# NSE2022_IMGPS_ver0.net
KiCad netlist of a schematic drawn in EAGLE
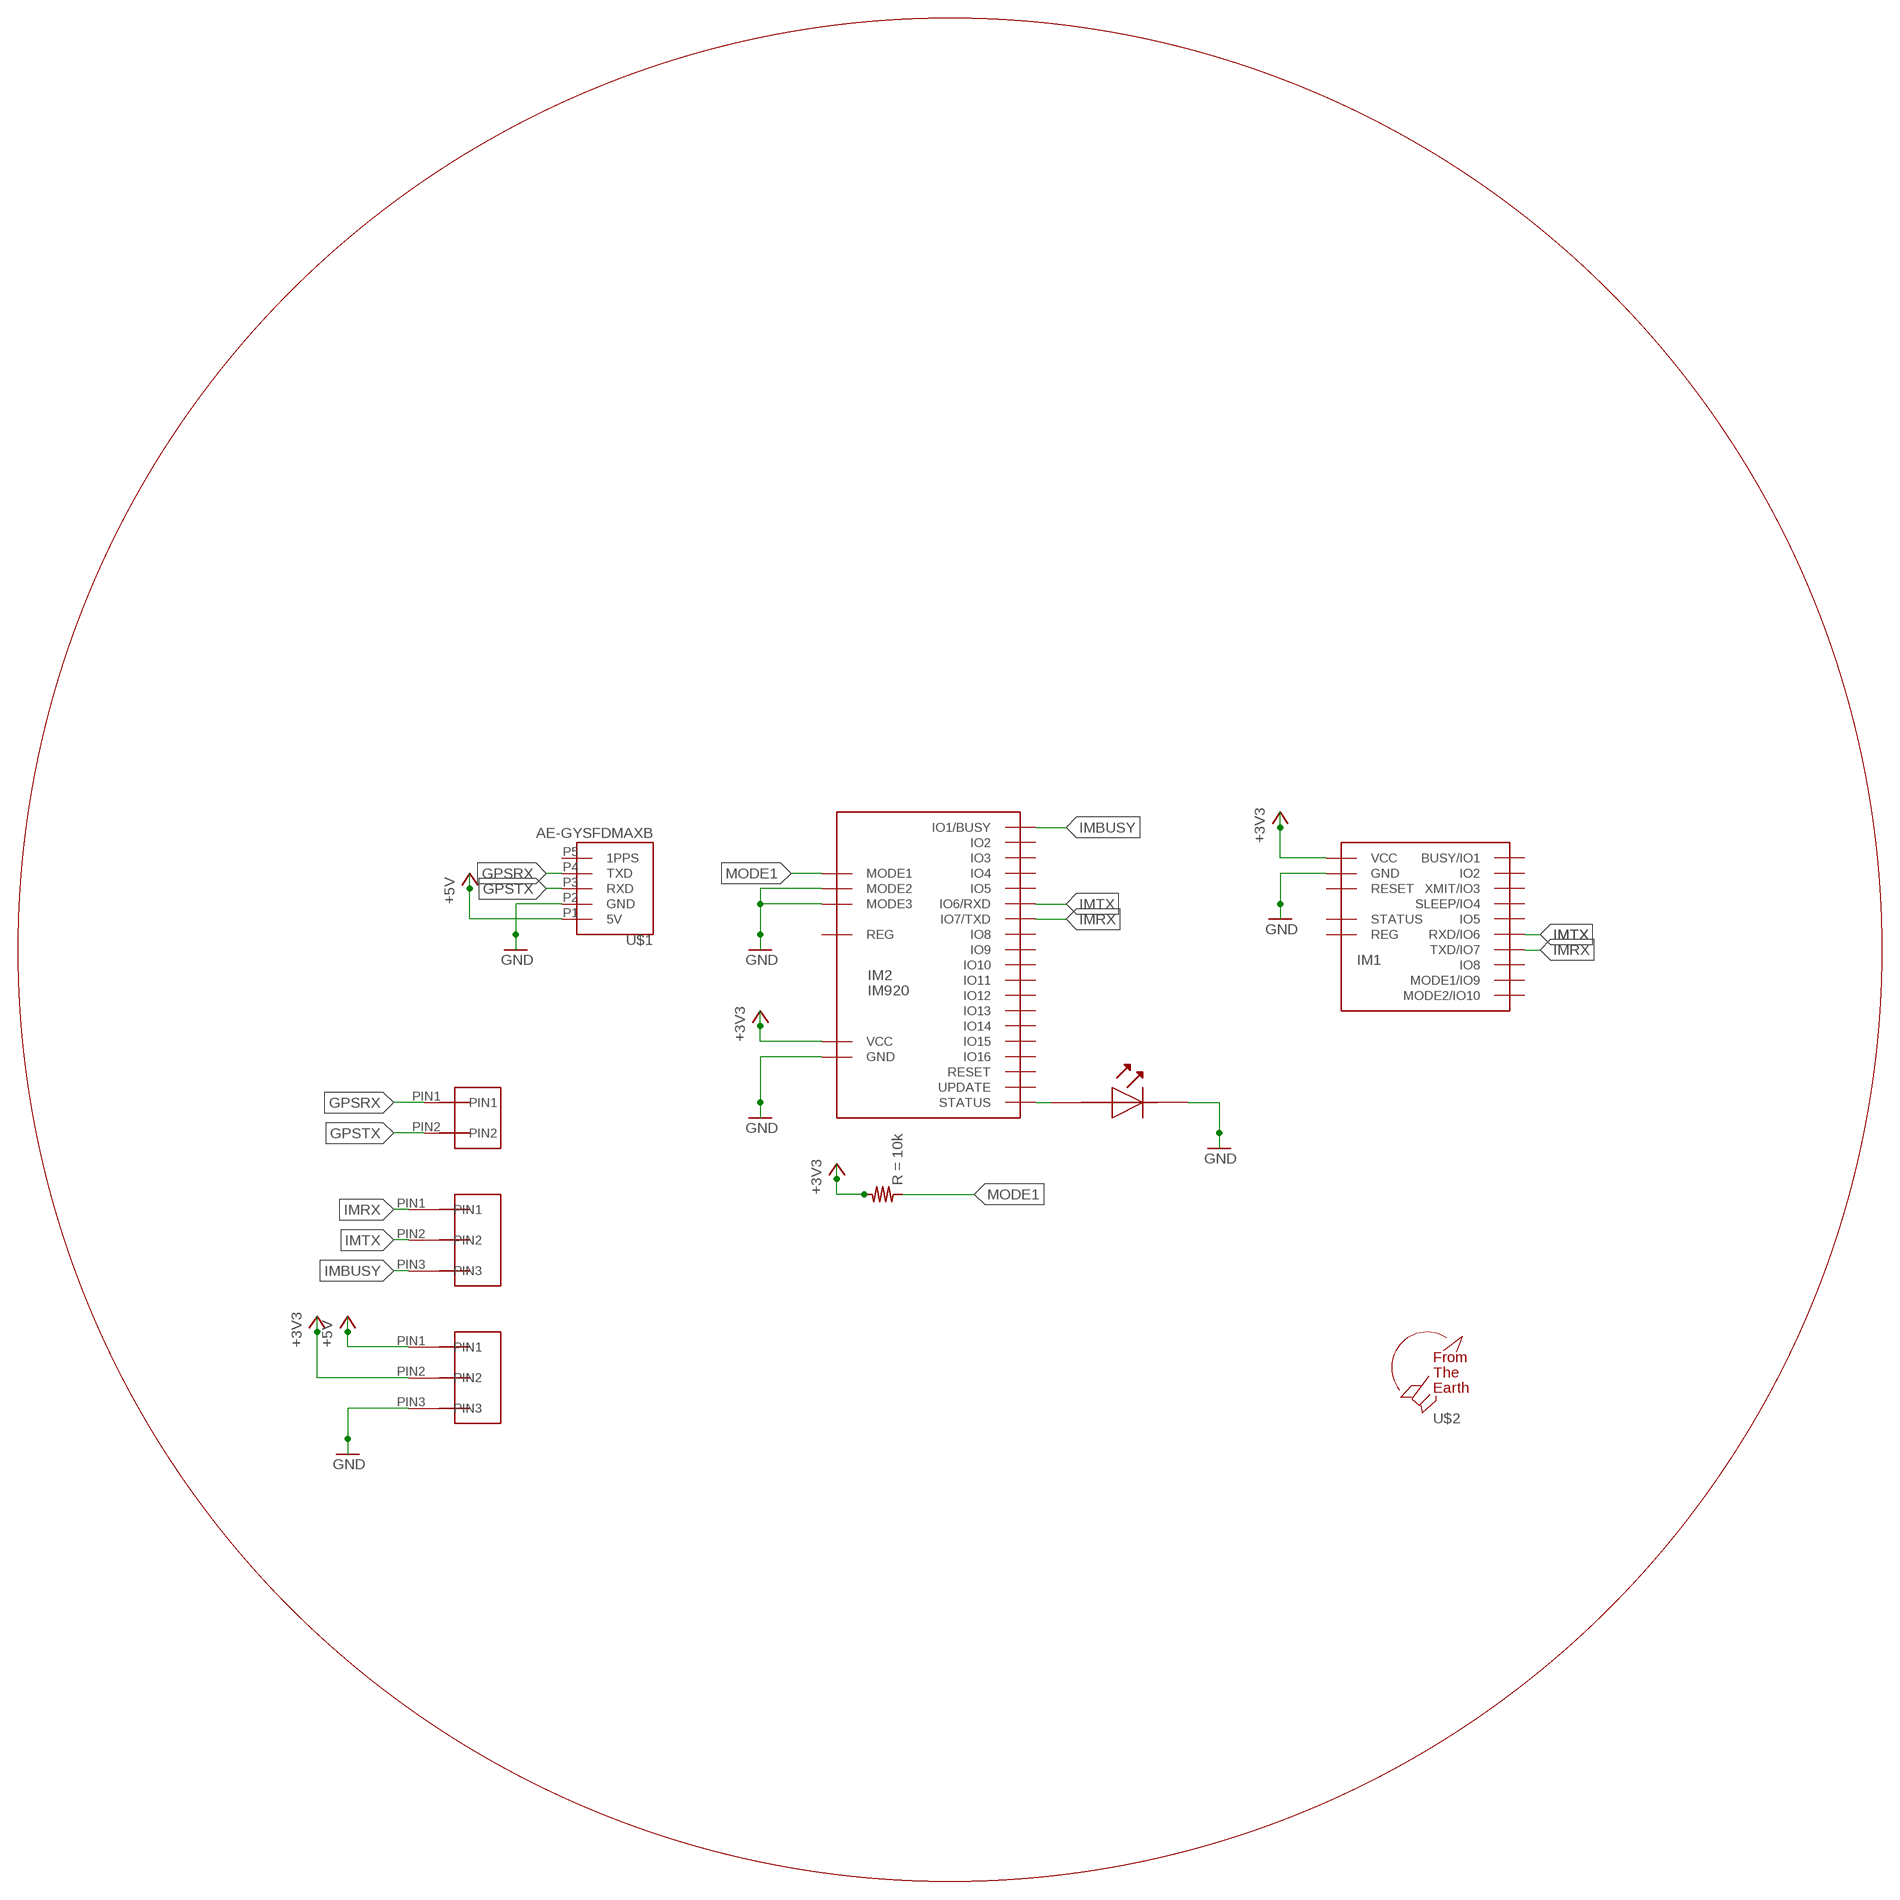
[diagram p0: schematic, sheet 1]

(export (version "E")
  (design (tool "Eeschema 10.0.6"))
  (components
    (comp (ref "IM1")
      (value "IM920C")
      (footprint "eagle-import:IM920C")
      (libsource (lib "eagle-import") (part "IM920C"))
    )
    (comp (ref "IM2")
      (value "IM920")
      (footprint "eagle-import:IM920")
      (libsource (lib "eagle-import") (part "IM920"))
    )
    (comp (ref "R4")
      (value "RESISTER")
      (footprint "eagle-import:REGISTER")
      (fields (field (name "R") "10k"))
      (libsource (lib "eagle-import") (part "RESISTER"))
    )
    (comp (ref "U$1")
      (value "AE-GYSFDMAXB")
      (footprint "eagle-import:AE-GYSFDMAXB")
      (libsource (lib "eagle-import") (part "AE-GYSFDMAXB"))
    )
    (comp (ref "U$2")
      (value "F.T.E.LOGO")
      (footprint "eagle-import:LOGO")
      (libsource (lib "eagle-import") (part "F.T.E.LOGO"))
    )
    (comp (ref "U$33")
      (value "2PIN")
      (footprint "eagle-import:2PIN")
      (libsource (lib "eagle-import") (part "2PIN"))
    )
    (comp (ref "U$47")
      (value "3PIN")
      (footprint "eagle-import:3PIN")
      (libsource (lib "eagle-import") (part "3PIN"))
    )
    (comp (ref "U$48")
      (value "3PIN")
      (footprint "eagle-import:3PIN")
      (libsource (lib "eagle-import") (part "3PIN"))
    )
    (comp (ref "U$54")
      (value "LED")
      (footprint "eagle-import:LED")
      (libsource (lib "eagle-import") (part "LED"))
    )
  )
  (nets
    (net (code "1") (name "+3V3") (class "Default")
      (node (ref "IM1") (pin "$P17") (pinfunction "VCC_$P17") (pintype "bidirectional"))
      (node (ref "IM2") (pin "IO23") (pinfunction "VCC_IO23") (pintype "bidirectional"))
      (node (ref "R4") (pin "B") (pinfunction "B_B") (pintype "bidirectional"))
      (node (ref "U$48") (pin "PIN2") (pinfunction "PIN2_PIN2") (pintype "bidirectional"))
    )
    (net (code "2") (name "+5V") (class "Default")
      (node (ref "U$1") (pin "P1") (pinfunction "5V_P1") (pintype "bidirectional"))
      (node (ref "U$48") (pin "PIN1") (pinfunction "PIN1_PIN1") (pintype "bidirectional"))
    )
    (net (code "3") (name "GND") (class "Default")
      (node (ref "IM1") (pin "$P18") (pinfunction "GND_$P18") (pintype "bidirectional"))
      (node (ref "IM2") (pin "IO18") (pinfunction "MODE2_IO18") (pintype "bidirectional"))
      (node (ref "IM2") (pin "IO19") (pinfunction "MODE3_IO19") (pintype "bidirectional"))
      (node (ref "IM2") (pin "IO24") (pinfunction "GND_IO24") (pintype "bidirectional"))
      (node (ref "U$1") (pin "P2") (pinfunction "GND_P2") (pintype "bidirectional"))
      (node (ref "U$48") (pin "PIN3") (pinfunction "PIN3_PIN3") (pintype "bidirectional"))
      (node (ref "U$54") (pin "PLUS") (pinfunction "OUT_PLUS") (pintype "bidirectional"))
    )
    (net (code "4") (name "GPSRX") (class "Default")
      (node (ref "U$1") (pin "P4") (pinfunction "TXD_P4") (pintype "bidirectional"))
      (node (ref "U$33") (pin "PIN1") (pinfunction "PIN1_PIN1") (pintype "bidirectional"))
    )
    (net (code "5") (name "GPSTX") (class "Default")
      (node (ref "U$1") (pin "P3") (pinfunction "RXD_P3") (pintype "bidirectional"))
      (node (ref "U$33") (pin "PIN2") (pinfunction "PIN2_PIN2") (pintype "bidirectional"))
    )
    (net (code "6") (name "IMBUSY") (class "Default")
      (node (ref "IM2") (pin "IO1") (pinfunction "IO1/BUSY_IO1") (pintype "bidirectional"))
      (node (ref "U$47") (pin "PIN3") (pinfunction "PIN3_PIN3") (pintype "bidirectional"))
    )
    (net (code "7") (name "IMRX") (class "Default")
      (node (ref "IM1") (pin "$P7") (pinfunction "TXD/IO7_$P7") (pintype "bidirectional"))
      (node (ref "IM2") (pin "IO7") (pinfunction "IO7/TXD_IO7") (pintype "bidirectional"))
      (node (ref "U$47") (pin "PIN1") (pinfunction "PIN1_PIN1") (pintype "bidirectional"))
    )
    (net (code "8") (name "IMTX") (class "Default")
      (node (ref "IM1") (pin "$P6") (pinfunction "RXD/IO6_$P6") (pintype "bidirectional"))
      (node (ref "IM2") (pin "IO6") (pinfunction "IO6/RXD_IO6") (pintype "bidirectional"))
      (node (ref "U$47") (pin "PIN2") (pinfunction "PIN2_PIN2") (pintype "bidirectional"))
    )
    (net (code "9") (name "MODE1") (class "Default")
      (node (ref "IM2") (pin "IO17") (pinfunction "MODE1_IO17") (pintype "bidirectional"))
      (node (ref "R4") (pin "A") (pinfunction "A_A") (pintype "bidirectional"))
    )
    (net (code "10") (name "Net-(IM2-STATUS)") (class "Default")
      (node (ref "IM2") (pin "IO21") (pinfunction "STATUS_IO21") (pintype "bidirectional"))
      (node (ref "U$54") (pin "MINUS") (pinfunction "IN_MINUS") (pintype "bidirectional"))
    )
    (net (code "11") (name "unconnected-(IM1-BUSY{slash}IO1-Pad$P1)") (class "Default")
      (node (ref "IM1") (pin "$P1") (pinfunction "BUSY/IO1_$P1") (pintype "bidirectional"))
    )
    (net (code "12") (name "unconnected-(IM1-IO2-Pad$P2)") (class "Default")
      (node (ref "IM1") (pin "$P2") (pinfunction "IO2_$P2") (pintype "bidirectional"))
    )
    (net (code "13") (name "unconnected-(IM1-IO5-Pad$P5)") (class "Default")
      (node (ref "IM1") (pin "$P5") (pinfunction "IO5_$P5") (pintype "bidirectional"))
    )
    (net (code "14") (name "unconnected-(IM1-IO8-Pad$P8)") (class "Default")
      (node (ref "IM1") (pin "$P8") (pinfunction "IO8_$P8") (pintype "bidirectional"))
    )
    (net (code "15") (name "unconnected-(IM1-MODE1{slash}IO9-Pad$P9)") (class "Default")
      (node (ref "IM1") (pin "$P9") (pinfunction "MODE1/IO9_$P9") (pintype "bidirectional"))
    )
    (net (code "16") (name "unconnected-(IM1-MODE2{slash}IO10-Pad$P10)") (class "Default")
      (node (ref "IM1") (pin "$P10") (pinfunction "MODE2/IO10_$P10") (pintype "bidirectional"))
    )
    (net (code "17") (name "unconnected-(IM1-REG-Pad$P16)") (class "Default")
      (node (ref "IM1") (pin "$P16") (pinfunction "REG_$P16") (pintype "bidirectional"))
    )
    (net (code "18") (name "unconnected-(IM1-RESET-Pad$P19)") (class "Default")
      (node (ref "IM1") (pin "$P19") (pinfunction "RESET_$P19") (pintype "bidirectional"))
    )
    (net (code "19") (name "unconnected-(IM1-SLEEP{slash}IO4-Pad$P4)") (class "Default")
      (node (ref "IM1") (pin "$P4") (pinfunction "SLEEP/IO4_$P4") (pintype "bidirectional"))
    )
    (net (code "20") (name "unconnected-(IM1-STATUS-Pad$P15)") (class "Default")
      (node (ref "IM1") (pin "$P15") (pinfunction "STATUS_$P15") (pintype "bidirectional"))
    )
    (net (code "21") (name "unconnected-(IM1-XMIT{slash}IO3-Pad$P3)") (class "Default")
      (node (ref "IM1") (pin "$P3") (pinfunction "XMIT/IO3_$P3") (pintype "bidirectional"))
    )
    (net (code "22") (name "unconnected-(IM2-PadIO2)") (class "Default")
      (node (ref "IM2") (pin "IO2") (pinfunction "IO2_IO2") (pintype "bidirectional"))
    )
    (net (code "23") (name "unconnected-(IM2-PadIO3)") (class "Default")
      (node (ref "IM2") (pin "IO3") (pinfunction "IO3_IO3") (pintype "bidirectional"))
    )
    (net (code "24") (name "unconnected-(IM2-PadIO4)") (class "Default")
      (node (ref "IM2") (pin "IO4") (pinfunction "IO4_IO4") (pintype "bidirectional"))
    )
    (net (code "25") (name "unconnected-(IM2-PadIO5)") (class "Default")
      (node (ref "IM2") (pin "IO5") (pinfunction "IO5_IO5") (pintype "bidirectional"))
    )
    (net (code "26") (name "unconnected-(IM2-PadIO8)") (class "Default")
      (node (ref "IM2") (pin "IO8") (pinfunction "IO8_IO8") (pintype "bidirectional"))
    )
    (net (code "27") (name "unconnected-(IM2-PadIO9)") (class "Default")
      (node (ref "IM2") (pin "IO9") (pinfunction "IO9_IO9") (pintype "bidirectional"))
    )
    (net (code "28") (name "unconnected-(IM2-PadIO10)") (class "Default")
      (node (ref "IM2") (pin "IO10") (pinfunction "IO10_IO10") (pintype "bidirectional"))
    )
    (net (code "29") (name "unconnected-(IM2-PadIO11)") (class "Default")
      (node (ref "IM2") (pin "IO11") (pinfunction "IO11_IO11") (pintype "bidirectional"))
    )
    (net (code "30") (name "unconnected-(IM2-PadIO12)") (class "Default")
      (node (ref "IM2") (pin "IO12") (pinfunction "IO12_IO12") (pintype "bidirectional"))
    )
    (net (code "31") (name "unconnected-(IM2-PadIO13)") (class "Default")
      (node (ref "IM2") (pin "IO13") (pinfunction "IO13_IO13") (pintype "bidirectional"))
    )
    (net (code "32") (name "unconnected-(IM2-PadIO14)") (class "Default")
      (node (ref "IM2") (pin "IO14") (pinfunction "IO14_IO14") (pintype "bidirectional"))
    )
    (net (code "33") (name "unconnected-(IM2-PadIO15)") (class "Default")
      (node (ref "IM2") (pin "IO15") (pinfunction "IO15_IO15") (pintype "bidirectional"))
    )
    (net (code "34") (name "unconnected-(IM2-PadIO16)") (class "Default")
      (node (ref "IM2") (pin "IO16") (pinfunction "IO16_IO16") (pintype "bidirectional"))
    )
    (net (code "35") (name "unconnected-(IM2-REG-PadIO22)") (class "Default")
      (node (ref "IM2") (pin "IO22") (pinfunction "REG_IO22") (pintype "bidirectional"))
    )
    (net (code "36") (name "unconnected-(IM2-RESET-PadIO25)") (class "Default")
      (node (ref "IM2") (pin "IO25") (pinfunction "RESET_IO25") (pintype "bidirectional"))
    )
    (net (code "37") (name "unconnected-(IM2-UPDATE-PadIO20)") (class "Default")
      (node (ref "IM2") (pin "IO20") (pinfunction "UPDATE_IO20") (pintype "bidirectional"))
    )
    (net (code "38") (name "unconnected-(U$1-1PPS-PadP5)") (class "Default")
      (node (ref "U$1") (pin "P5") (pinfunction "1PPS_P5") (pintype "bidirectional"))
    )
  )
)
